# 12V-Power-Supplies.net
KiCad netlist of a schematic drawn in Altium Designer
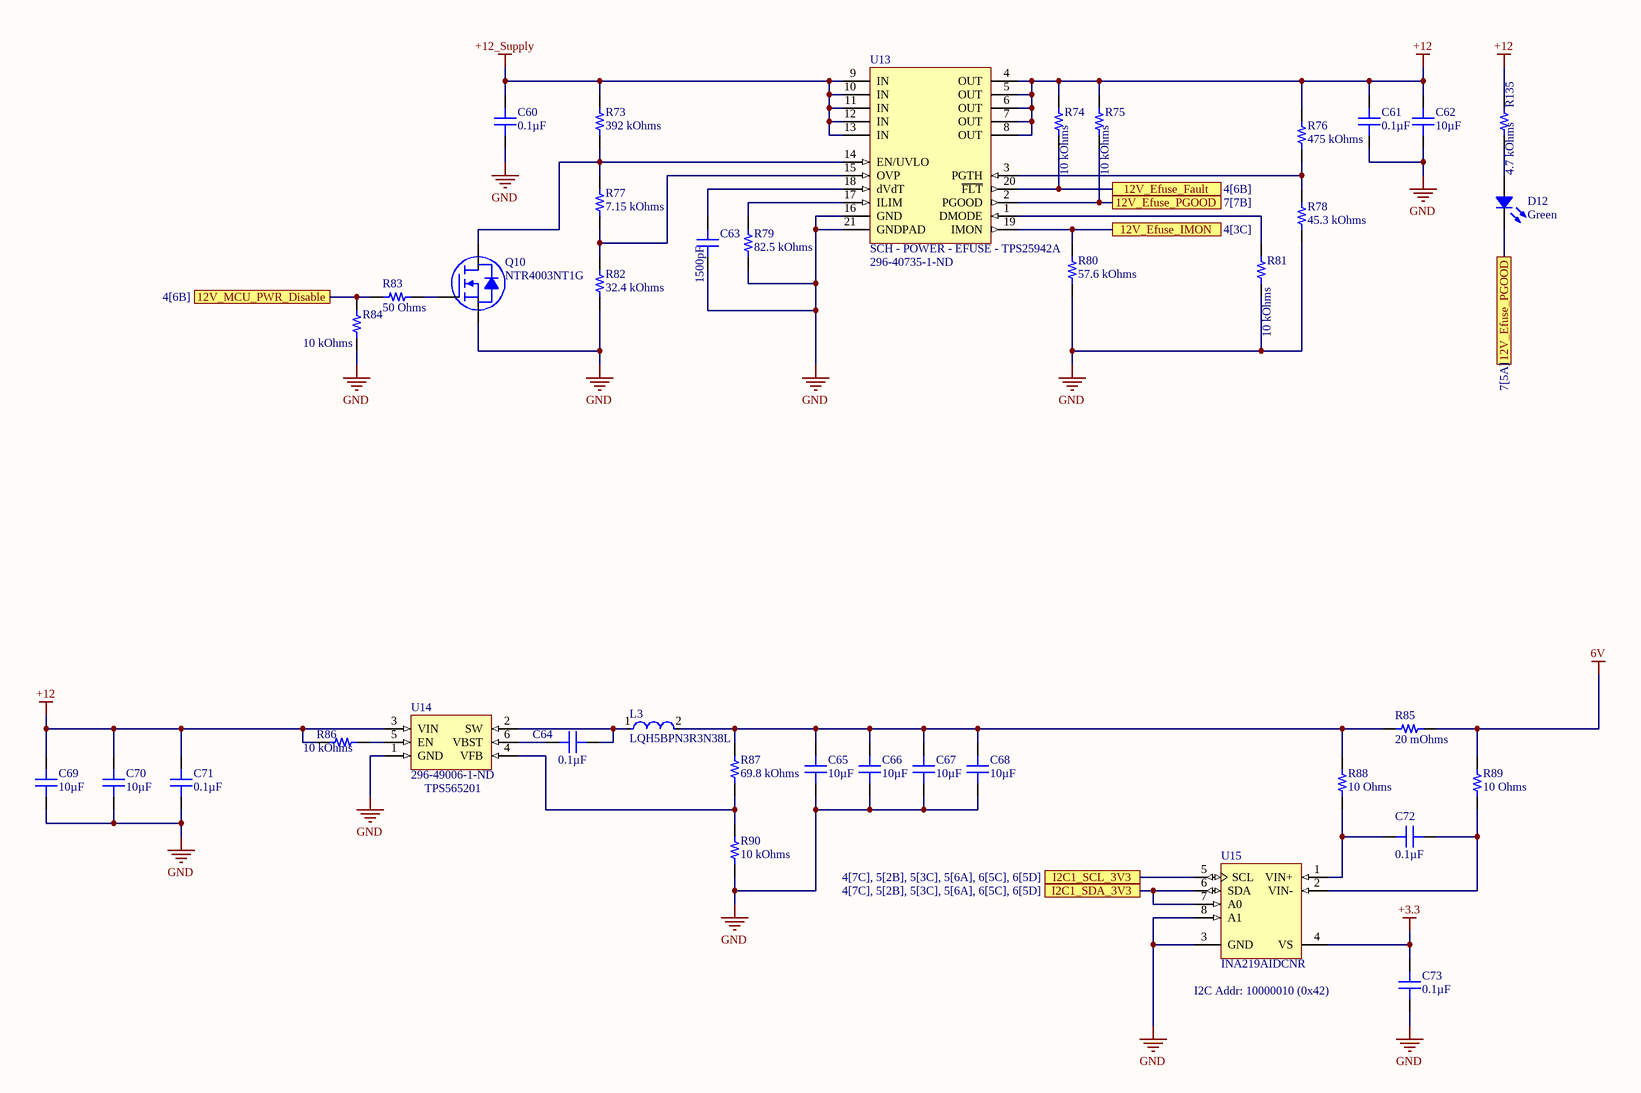
[diagram p0: 12V-Power-Supplies.SchDoc]

(export (version "E")
  (design (tool "Eeschema 10.0.6"))
  (components
    (comp (ref "C60")
      (value "0.1µF")
      (footprint "CAP 0603_1608")
      (description "CAP CER 0.1UF 25V X7R 0603")
      (fields
        (field (name "PART NUMBER") "CL10B104KA8WPNC")
        (field (name "MANUFACTURER") "Samsung Electro-Mechanics")
      )
      (libsource (lib "Celestial Altium Library - altium_library") (part "Capacitor"))
    )
    (comp (ref "C61")
      (value "0.1µF")
      (footprint "CAP 0603_1608")
      (description "CAP CER 0.1UF 25V X7R 0603")
      (fields
        (field (name "PART NUMBER") "CL10B104KA8WPNC")
        (field (name "MANUFACTURER") "Samsung Electro-Mechanics")
      )
      (libsource (lib "Celestial Altium Library - altium_library") (part "Capacitor"))
    )
    (comp (ref "C62")
      (value "10µF")
      (footprint "CAP 0805_2012")
      (description "CAP CER 10UF 16V X5R 0805")
      (fields (field (name "PART NUMBER") "CC0805KKX5R7BB106") (field (name "MANUFACTURER") "Yageo"))
      (libsource (lib "Celestial Altium Library - altium_library") (part "Capacitor"))
    )
    (comp (ref "C63")
      (value "1500pF")
      (footprint "CAP 0603_1608")
      (description "CAP CER 1500PF 25V X7R 0603")
      (fields (field (name "PART NUMBER") "CC0603JRX7R8BB152") (field (name "MANUFACTURER") "Yageo"))
      (libsource (lib "Celestial Altium Library - altium_library") (part "Capacitor"))
    )
    (comp (ref "C64")
      (value "0.1µF")
      (footprint "CAP 0603_1608")
      (description "CAP CER 0.1UF 25V X7R 0603")
      (fields
        (field (name "PART NUMBER") "CL10B104KA8WPNC")
        (field (name "MANUFACTURER") "Samsung Electro-Mechanics")
      )
      (libsource (lib "Celestial Altium Library - altium_library") (part "Capacitor"))
    )
    (comp (ref "C65")
      (value "10µF")
      (footprint "CAP 0805_2012")
      (description "CAP CER 10UF 16V X5R 0805")
      (fields (field (name "PART NUMBER") "CC0805KKX5R7BB106") (field (name "MANUFACTURER") "Yageo"))
      (libsource (lib "Celestial Altium Library - altium_library") (part "Capacitor"))
    )
    (comp (ref "C66")
      (value "10µF")
      (footprint "CAP 0805_2012")
      (description "CAP CER 10UF 16V X5R 0805")
      (fields (field (name "PART NUMBER") "CC0805KKX5R7BB106") (field (name "MANUFACTURER") "Yageo"))
      (libsource (lib "Celestial Altium Library - altium_library") (part "Capacitor"))
    )
    (comp (ref "C67")
      (value "10µF")
      (footprint "CAP 0805_2012")
      (description "CAP CER 10UF 16V X5R 0805")
      (fields (field (name "PART NUMBER") "CC0805KKX5R7BB106") (field (name "MANUFACTURER") "Yageo"))
      (libsource (lib "Celestial Altium Library - altium_library") (part "Capacitor"))
    )
    (comp (ref "C68")
      (value "10µF")
      (footprint "CAP 0805_2012")
      (description "CAP CER 10UF 16V X5R 0805")
      (fields (field (name "PART NUMBER") "CC0805KKX5R7BB106") (field (name "MANUFACTURER") "Yageo"))
      (libsource (lib "Celestial Altium Library - altium_library") (part "Capacitor"))
    )
    (comp (ref "C69")
      (value "10µF")
      (footprint "CAP 0805_2012")
      (description "CAP CER 10UF 16V X5R 0805")
      (fields (field (name "PART NUMBER") "CC0805KKX5R7BB106") (field (name "MANUFACTURER") "Yageo"))
      (libsource (lib "Celestial Altium Library - altium_library") (part "Capacitor"))
    )
    (comp (ref "C70")
      (value "10µF")
      (footprint "CAP 0805_2012")
      (description "CAP CER 10UF 16V X5R 0805")
      (fields (field (name "PART NUMBER") "CC0805KKX5R7BB106") (field (name "MANUFACTURER") "Yageo"))
      (libsource (lib "Celestial Altium Library - altium_library") (part "Capacitor"))
    )
    (comp (ref "C71")
      (value "0.1µF")
      (footprint "CAP 0603_1608")
      (description "CAP CER 0.1UF 25V X7R 0603")
      (fields
        (field (name "PART NUMBER") "CL10B104KA8WPNC")
        (field (name "MANUFACTURER") "Samsung Electro-Mechanics")
      )
      (libsource (lib "Celestial Altium Library - altium_library") (part "Capacitor"))
    )
    (comp (ref "C72")
      (value "0.1µF")
      (footprint "CAP 0603_1608")
      (description "CAP CER 0.1UF 25V X7R 0603")
      (fields
        (field (name "PART NUMBER") "CL10B104KA8WPNC")
        (field (name "MANUFACTURER") "Samsung Electro-Mechanics")
      )
      (libsource (lib "Celestial Altium Library - altium_library") (part "Capacitor"))
    )
    (comp (ref "C73")
      (value "0.1µF")
      (footprint "CAP 0603_1608")
      (description "CAP CER 0.1UF 25V X7R 0603")
      (fields
        (field (name "PART NUMBER") "CL10B104KA8WPNC")
        (field (name "MANUFACTURER") "Samsung Electro-Mechanics")
      )
      (libsource (lib "Celestial Altium Library - altium_library") (part "Capacitor"))
    )
    (comp (ref "D12")
      (value "Green")
      (footprint "LED 0603_1608 GREEN")
      (description "LED GREEN CLEAR CHIP SMD")
      (fields (field (name "PART NUMBER") "LTST-C193KGKT-5A") (field (name "MANUFACTURER") "Lite-On Inc."))
      (libsource (lib "Celestial Altium Library - altium_library") (part "LED"))
    )
    (comp (ref "L3")
      (value "LQH5BPN3R3N38L")
      (footprint "FP-LQH5BPN_38-MFG")
      (description "Wire Wound Ferrite Inductor for Power Lines 3.3μH ±30% 0.0252Ω 4000mA 2020")
      (fields (field (name "TOLERANCE") "30%"))
      (libsource (lib "Altium Content Vault") (part "725321dda6339637d4d059423bc1c3c"))
    )
    (comp (ref "Q10")
      (value "NTR4003NT1G")
      (footprint "ON SEMI SOT-23-3")
      (description "MOSFET N-CH 30V 500MA SOT-23")
      (fields (field (name "MANUFACTURER") "ON Semiconductor"))
      (libsource (lib "Celestial Altium Library - altium_library") (part "ON SEMI MOSFET N-CH SOT-23-3"))
    )
    (comp (ref "R73")
      (value "392 kOhms")
      (footprint "RES 0603_1608")
      (description "RES 392K OHM 1% 1/10W 0603")
      (fields
        (field (name "PART NUMBER") "RMCF0603FT392K")
        (field (name "MANUFACTURER") "Stackpole Electronics Inc")
      )
      (libsource (lib "Celestial Altium Library - altium_library") (part "Resistor"))
    )
    (comp (ref "R74")
      (value "10 kOhms")
      (footprint "RES 0603_1608")
      (description "RES 10K OHM 5% 1/10W 0603")
      (fields
        (field (name "PART NUMBER") "RMCF0603JT10K0")
        (field (name "MANUFACTURER") "Stackpole Electronics Inc")
      )
      (libsource (lib "Celestial Altium Library - altium_library") (part "Resistor"))
    )
    (comp (ref "R75")
      (value "10 kOhms")
      (footprint "RES 0603_1608")
      (description "RES 10K OHM 5% 1/10W 0603")
      (fields
        (field (name "PART NUMBER") "RMCF0603JT10K0")
        (field (name "MANUFACTURER") "Stackpole Electronics Inc")
      )
      (libsource (lib "Celestial Altium Library - altium_library") (part "Resistor"))
    )
    (comp (ref "R76")
      (value "475 kOhms")
      (footprint "RES 0603_1608")
      (description "RES 475K OHM 1% 1/10W 0603")
      (fields
        (field (name "PART NUMBER") "RMCF0603FT475K")
        (field (name "MANUFACTURER") "Stackpole Electronics Inc")
      )
      (libsource (lib "Celestial Altium Library - altium_library") (part "Resistor"))
    )
    (comp (ref "R77")
      (value "7.15 kOhms")
      (footprint "RES 0603_1608")
      (description "RES SMD 7.15K OHM 0.1% 1/5W 0603")
      (fields
        (field (name "PART NUMBER") "ERJ-PB3B7151V")
        (field (name "MANUFACTURER") "Panasonic Electronic Components")
      )
      (libsource (lib "Celestial Altium Library - altium_library") (part "Resistor"))
    )
    (comp (ref "R78")
      (value "45.3 kOhms")
      (footprint "RES 0603_1608")
      (description "RES 45.3K OHM 1% 1/10W 0603")
      (fields
        (field (name "PART NUMBER") "RMCF0603FT45K3")
        (field (name "MANUFACTURER") "Stackpole Electronics Inc")
      )
      (libsource (lib "Celestial Altium Library - altium_library") (part "Resistor"))
    )
    (comp (ref "R79")
      (value "82.5 kOhms")
      (footprint "RES 0603_1608")
      (description "RES 82.5K OHM 1% 1/10W 0603")
      (fields
        (field (name "PART NUMBER") "RMCF0603FT82K5")
        (field (name "MANUFACTURER") "Stackpole Electronics Inc")
      )
      (libsource (lib "Celestial Altium Library - altium_library") (part "Resistor"))
    )
    (comp (ref "R80")
      (value "57.6 kOhms")
      (footprint "RES 0603_1608")
      (description "RES 57.6K OHM 1% 1/10W 0603")
      (fields
        (field (name "PART NUMBER") "RMCF0603FT57K6")
        (field (name "MANUFACTURER") "Stackpole Electronics Inc")
      )
      (libsource (lib "Celestial Altium Library - altium_library") (part "Resistor"))
    )
    (comp (ref "R81")
      (value "10 kOhms")
      (footprint "RES 0603_1608")
      (description "RES 10K OHM 5% 1/10W 0603")
      (fields
        (field (name "PART NUMBER") "RMCF0603JT10K0")
        (field (name "MANUFACTURER") "Stackpole Electronics Inc")
      )
      (libsource (lib "Celestial Altium Library - altium_library") (part "Resistor"))
    )
    (comp (ref "R82")
      (value "32.4 kOhms")
      (footprint "RES 0603_1608")
      (description "RES SMD 32.4K OHM 0.1% 1/5W 0603")
      (fields
        (field (name "PART NUMBER") "ERJ-PB3B3242V")
        (field (name "MANUFACTURER") "Panasonic Electronic Components")
      )
      (libsource (lib "Celestial Altium Library - altium_library") (part "Resistor"))
    )
    (comp (ref "R83")
      (value "50 Ohms")
      (footprint "RES 0603_1608")
      (description "RES SMD 50 OHM 1% 1/10W 0603")
      (fields (field (name "PART NUMBER") "CRCW060350R0FKEA") (field (name "MANUFACTURER") "Vishay Dale"))
      (libsource (lib "Celestial Altium Library - altium_library") (part "Resistor"))
    )
    (comp (ref "R84")
      (value "10 kOhms")
      (footprint "RES 0603_1608")
      (description "RES 10K OHM 5% 1/10W 0603")
      (fields
        (field (name "PART NUMBER") "RMCF0603JT10K0")
        (field (name "MANUFACTURER") "Stackpole Electronics Inc")
      )
      (libsource (lib "Celestial Altium Library - altium_library") (part "Resistor"))
    )
    (comp (ref "R85")
      (value "20 mOhms")
      (footprint "RES 0805_2012")
      (description "0805 CURRENT SENSING RES. 0.5%,")
      (fields
        (field (name "PART NUMBER") "ERJ-6CWDR020V")
        (field (name "MANUFACTURER") "Panasonic Electronic Components")
      )
      (libsource (lib "Celestial Altium Library - altium_library") (part "Resistor"))
    )
    (comp (ref "R86")
      (value "10 kOhms")
      (footprint "RES 0603_1608")
      (description "RES 10K OHM 5% 1/10W 0603")
      (fields
        (field (name "PART NUMBER") "RMCF0603JT10K0")
        (field (name "MANUFACTURER") "Stackpole Electronics Inc")
      )
      (libsource (lib "Celestial Altium Library - altium_library") (part "Resistor"))
    )
    (comp (ref "R87")
      (value "69.8 kOhms")
      (footprint "RES 0603_1608")
      (description "RES 69.8K OHM 1% 1/10W 0603")
      (fields
        (field (name "PART NUMBER") "RMCF0603FT69K8")
        (field (name "MANUFACTURER") "Stackpole Electronics Inc")
      )
      (libsource (lib "Celestial Altium Library - altium_library") (part "Resistor"))
    )
    (comp (ref "R88")
      (value "10 Ohms")
      (footprint "RES 0603_1608")
      (description "CRGCQ 0603 10R 1%")
      (fields
        (field (name "PART NUMBER") "CRGCQ0603F10R")
        (field (name "MANUFACTURER") "TE Connectivity Passive Product")
      )
      (libsource (lib "Celestial Altium Library - altium_library") (part "Resistor"))
    )
    (comp (ref "R89")
      (value "10 Ohms")
      (footprint "RES 0603_1608")
      (description "CRGCQ 0603 10R 1%")
      (fields
        (field (name "PART NUMBER") "CRGCQ0603F10R")
        (field (name "MANUFACTURER") "TE Connectivity Passive Product")
      )
      (libsource (lib "Celestial Altium Library - altium_library") (part "Resistor"))
    )
    (comp (ref "R90")
      (value "10 kOhms")
      (footprint "RES 0603_1608")
      (description "RES 10K OHM 1% 1/10W 0603")
      (fields
        (field (name "PART NUMBER") "RMCF0603FT10K0")
        (field (name "MANUFACTURER") "Stackpole Electronics Inc")
      )
      (libsource (lib "Celestial Altium Library - altium_library") (part "Resistor"))
    )
    (comp (ref "R135")
      (value "4.7 kOhms")
      (footprint "RES 0603_1608")
      (description "RES 4.7K OHM 1% 1/10W 0603")
      (fields
        (field (name "PART NUMBER") "RMCF0603FT4K70")
        (field (name "MANUFACTURER") "Stackpole Electronics Inc")
      )
      (libsource (lib "Celestial Altium Library - altium_library") (part "Resistor"))
    )
    (comp (ref "U13")
      (value "SCH - POWER - EFUSE - TPS25942A")
      (footprint "PCB - LEADLESS - QFN - TI 20-WQFN")
      (fields (field (name "SUPPLIER PART NUMBER 1") "296-40735-1-ND"))
      (libsource (lib "HAB_ICs") (part "SCH - POWER - EFUSE - TPS25942A"))
    )
    (comp (ref "U14")
      (value "SCH - REGULATOR - BUCK - TI TPS565201DDCR")
      (footprint "PCB - LEADS - SOT- TI TSOT-23-6")
      (fields (field (name "SUPPLIER PART NUMBER 1") "296-49006-1-ND"))
      (libsource (lib "HAB_ICs") (part "SCH - REGULATOR - BUCK - TI TPS565201DDCR"))
    )
    (comp (ref "U15")
      (value "INA219AIDCNR")
      (footprint "DCN0008A_M")
      (fields (field (name "MANUFACTURER") "Texas Instruments"))
      (libsource (lib "Altium Content Vault") (part "TI-INA219DCN8"))
    )
  )
  (nets
    (net (code "1") (name "+3.3") (class "Default")
      (node (ref "C73") (pin "2") (pinfunction "2_2") (pintype "passive"))
      (node (ref "U15") (pin "4") (pinfunction "VS_4") (pintype "power_in"))
    )
    (net (code "2") (name "+12") (class "Default")
      (node (ref "C61") (pin "2") (pinfunction "2_2") (pintype "passive"))
      (node (ref "C62") (pin "2") (pinfunction "2_2") (pintype "passive"))
      (node (ref "C69") (pin "2") (pinfunction "2_2") (pintype "passive"))
      (node (ref "C70") (pin "2") (pinfunction "2_2") (pintype "passive"))
      (node (ref "C71") (pin "1") (pinfunction "1_1") (pintype "passive"))
      (node (ref "R135") (pin "2") (pinfunction "2_2") (pintype "passive"))
      (node (ref "R74") (pin "2") (pinfunction "2_2") (pintype "passive"))
      (node (ref "R75") (pin "2") (pinfunction "2_2") (pintype "passive"))
      (node (ref "R76") (pin "2") (pinfunction "2_2") (pintype "passive"))
      (node (ref "R86") (pin "1") (pinfunction "1_1") (pintype "passive"))
      (node (ref "U13") (pin "4") (pinfunction "OUT_4") (pintype "power_in"))
      (node (ref "U13") (pin "5") (pinfunction "OUT_5") (pintype "power_in"))
      (node (ref "U13") (pin "6") (pinfunction "OUT_6") (pintype "power_in"))
      (node (ref "U13") (pin "7") (pinfunction "OUT_7") (pintype "power_in"))
      (node (ref "U13") (pin "8") (pinfunction "OUT_8") (pintype "power_in"))
      (node (ref "U14") (pin "3") (pinfunction "VIN_3") (pintype "input"))
    )
    (net (code "3") (name "+12_Supply") (class "Default")
      (node (ref "C60") (pin "2") (pinfunction "2_2") (pintype "passive"))
      (node (ref "R73") (pin "2") (pinfunction "2_2") (pintype "passive"))
      (node (ref "U13") (pin "10") (pinfunction "IN_10") (pintype "power_in"))
      (node (ref "U13") (pin "11") (pinfunction "IN_11") (pintype "power_in"))
      (node (ref "U13") (pin "12") (pinfunction "IN_12") (pintype "power_in"))
      (node (ref "U13") (pin "13") (pinfunction "IN_13") (pintype "power_in"))
      (node (ref "U13") (pin "9") (pinfunction "IN_9") (pintype "power_in"))
    )
    (net (code "4") (name "/12V_Efuse_Fault") (class "Default")
      (node (ref "R74") (pin "1") (pinfunction "1_1") (pintype "passive"))
      (node (ref "U13") (pin "20") (pinfunction "~{FLT}_20") (pintype "output"))
    )
    (net (code "5") (name "/12V_Efuse_IMON") (class "Default")
      (node (ref "R80") (pin "2") (pinfunction "2_2") (pintype "passive"))
      (node (ref "U13") (pin "19") (pinfunction "IMON_19") (pintype "output"))
    )
    (net (code "6") (name "/12V_Efuse_PGOOD") (class "Default")
      (node (ref "D12") (pin "2") (pinfunction "2_2") (pintype "passive"))
      (node (ref "R75") (pin "1") (pinfunction "1_1") (pintype "passive"))
      (node (ref "U13") (pin "2") (pinfunction "PGOOD_2") (pintype "output"))
    )
    (net (code "7") (name "/12V_MCU_PWR_Disable") (class "Default")
      (node (ref "R83") (pin "2") (pinfunction "2_2") (pintype "passive"))
      (node (ref "R84") (pin "2") (pinfunction "2_2") (pintype "passive"))
    )
    (net (code "8") (name "/I2C1_SCL_3V3") (class "Default")
      (node (ref "U15") (pin "5") (pinfunction "SCL_5") (pintype "bidirectional"))
    )
    (net (code "9") (name "/I2C1_SDA_3V3") (class "Default")
      (node (ref "U15") (pin "6") (pinfunction "SDA_6") (pintype "bidirectional"))
      (node (ref "U15") (pin "7") (pinfunction "A0_7") (pintype "input"))
    )
    (net (code "10") (name "6V") (class "Default")
      (node (ref "R85") (pin "2") (pinfunction "2_2") (pintype "passive"))
      (node (ref "R89") (pin "2") (pinfunction "2_2") (pintype "passive"))
    )
    (net (code "11") (name "GND") (class "Default")
      (node (ref "C60") (pin "1") (pinfunction "1_1") (pintype "passive"))
      (node (ref "C61") (pin "1") (pinfunction "1_1") (pintype "passive"))
      (node (ref "C62") (pin "1") (pinfunction "1_1") (pintype "passive"))
      (node (ref "C63") (pin "1") (pinfunction "1_1") (pintype "passive"))
      (node (ref "C65") (pin "1") (pinfunction "1_1") (pintype "passive"))
      (node (ref "C66") (pin "1") (pinfunction "1_1") (pintype "passive"))
      (node (ref "C67") (pin "1") (pinfunction "1_1") (pintype "passive"))
      (node (ref "C68") (pin "1") (pinfunction "1_1") (pintype "passive"))
      (node (ref "C69") (pin "1") (pinfunction "1_1") (pintype "passive"))
      (node (ref "C70") (pin "1") (pinfunction "1_1") (pintype "passive"))
      (node (ref "C71") (pin "2") (pinfunction "2_2") (pintype "passive"))
      (node (ref "C73") (pin "1") (pinfunction "1_1") (pintype "passive"))
      (node (ref "Q10") (pin "2") (pinfunction "S_2") (pintype "passive"))
      (node (ref "R78") (pin "1") (pinfunction "1_1") (pintype "passive"))
      (node (ref "R79") (pin "1") (pinfunction "1_1") (pintype "passive"))
      (node (ref "R80") (pin "1") (pinfunction "1_1") (pintype "passive"))
      (node (ref "R81") (pin "1") (pinfunction "1_1") (pintype "passive"))
      (node (ref "R82") (pin "1") (pinfunction "1_1") (pintype "passive"))
      (node (ref "R84") (pin "1") (pinfunction "1_1") (pintype "passive"))
      (node (ref "R90") (pin "1") (pinfunction "1_1") (pintype "passive"))
      (node (ref "U13") (pin "16") (pinfunction "GND_16") (pintype "power_in"))
      (node (ref "U13") (pin "21") (pinfunction "GNDPAD_21") (pintype "power_in"))
      (node (ref "U14") (pin "1") (pinfunction "GND_1") (pintype "input"))
      (node (ref "U15") (pin "3") (pinfunction "GND_3") (pintype "power_in"))
      (node (ref "U15") (pin "8") (pinfunction "A1_8") (pintype "input"))
    )
    (net (code "12") (name "Net-(C65-Pad2)") (class "Default")
      (node (ref "C65") (pin "2") (pinfunction "2_2") (pintype "passive"))
      (node (ref "C66") (pin "2") (pinfunction "2_2") (pintype "passive"))
      (node (ref "C67") (pin "2") (pinfunction "2_2") (pintype "passive"))
      (node (ref "C68") (pin "2") (pinfunction "2_2") (pintype "passive"))
      (node (ref "L3") (pin "2") (pinfunction "2_2") (pintype "passive"))
      (node (ref "R85") (pin "1") (pinfunction "1_1") (pintype "passive"))
      (node (ref "R87") (pin "2") (pinfunction "2_2") (pintype "passive"))
      (node (ref "R88") (pin "2") (pinfunction "2_2") (pintype "passive"))
    )
    (net (code "13") (name "Net-(D12-Pad1)") (class "Default")
      (node (ref "D12") (pin "1") (pinfunction "1_1") (pintype "passive"))
      (node (ref "R135") (pin "1") (pinfunction "1_1") (pintype "passive"))
    )
    (net (code "14") (name "Net-(Q10-D)") (class "Default")
      (node (ref "Q10") (pin "3") (pinfunction "D_3") (pintype "passive"))
      (node (ref "R73") (pin "1") (pinfunction "1_1") (pintype "passive"))
      (node (ref "R77") (pin "2") (pinfunction "2_2") (pintype "passive"))
      (node (ref "U13") (pin "14") (pinfunction "EN/UVLO_14") (pintype "input"))
    )
    (net (code "15") (name "Net-(Q10-G)") (class "Default")
      (node (ref "Q10") (pin "1") (pinfunction "G_1") (pintype "passive"))
      (node (ref "R83") (pin "1") (pinfunction "1_1") (pintype "passive"))
    )
    (net (code "16") (name "Net-(U13-DMODE)") (class "Default")
      (node (ref "R81") (pin "2") (pinfunction "2_2") (pintype "passive"))
      (node (ref "U13") (pin "1") (pinfunction "DMODE_1") (pintype "input"))
    )
    (net (code "17") (name "Net-(U13-ILIM)") (class "Default")
      (node (ref "R79") (pin "2") (pinfunction "2_2") (pintype "passive"))
      (node (ref "U13") (pin "17") (pinfunction "ILIM_17") (pintype "input"))
    )
    (net (code "18") (name "Net-(U13-OVP)") (class "Default")
      (node (ref "R77") (pin "1") (pinfunction "1_1") (pintype "passive"))
      (node (ref "R82") (pin "2") (pinfunction "2_2") (pintype "passive"))
      (node (ref "U13") (pin "15") (pinfunction "OVP_15") (pintype "input"))
    )
    (net (code "19") (name "Net-(U13-PGTH)") (class "Default")
      (node (ref "R76") (pin "1") (pinfunction "1_1") (pintype "passive"))
      (node (ref "R78") (pin "2") (pinfunction "2_2") (pintype "passive"))
      (node (ref "U13") (pin "3") (pinfunction "PGTH_3") (pintype "input"))
    )
    (net (code "20") (name "Net-(U13-dVdT)") (class "Default")
      (node (ref "C63") (pin "2") (pinfunction "2_2") (pintype "passive"))
      (node (ref "U13") (pin "18") (pinfunction "dVdT_18") (pintype "input"))
    )
    (net (code "21") (name "Net-(U14-EN)") (class "Default")
      (node (ref "R86") (pin "2") (pinfunction "2_2") (pintype "passive"))
      (node (ref "U14") (pin "5") (pinfunction "EN_5") (pintype "input"))
    )
    (net (code "22") (name "Net-(U14-SW)") (class "Default")
      (node (ref "C64") (pin "1") (pinfunction "1_1") (pintype "passive"))
      (node (ref "L3") (pin "1") (pinfunction "1_1") (pintype "passive"))
      (node (ref "U14") (pin "2") (pinfunction "SW_2") (pintype "input"))
    )
    (net (code "23") (name "Net-(U14-VBST)") (class "Default")
      (node (ref "C64") (pin "2") (pinfunction "2_2") (pintype "passive"))
      (node (ref "U14") (pin "6") (pinfunction "VBST_6") (pintype "input"))
    )
    (net (code "24") (name "Net-(U14-VFB)") (class "Default")
      (node (ref "R87") (pin "1") (pinfunction "1_1") (pintype "passive"))
      (node (ref "R90") (pin "2") (pinfunction "2_2") (pintype "passive"))
      (node (ref "U14") (pin "4") (pinfunction "VFB_4") (pintype "input"))
    )
    (net (code "25") (name "Net-(U15-VIN+)") (class "Default")
      (node (ref "C72") (pin "2") (pinfunction "2_2") (pintype "passive"))
      (node (ref "R88") (pin "1") (pinfunction "1_1") (pintype "passive"))
      (node (ref "U15") (pin "1") (pinfunction "VIN+_1") (pintype "input"))
    )
    (net (code "26") (name "Net-(U15-VIN-)") (class "Default")
      (node (ref "C72") (pin "1") (pinfunction "1_1") (pintype "passive"))
      (node (ref "R89") (pin "1") (pinfunction "1_1") (pintype "passive"))
      (node (ref "U15") (pin "2") (pinfunction "VIN-_2") (pintype "input"))
    )
  )
)
